# board.net
KiCad netlist of a schematic drawn in EAGLE
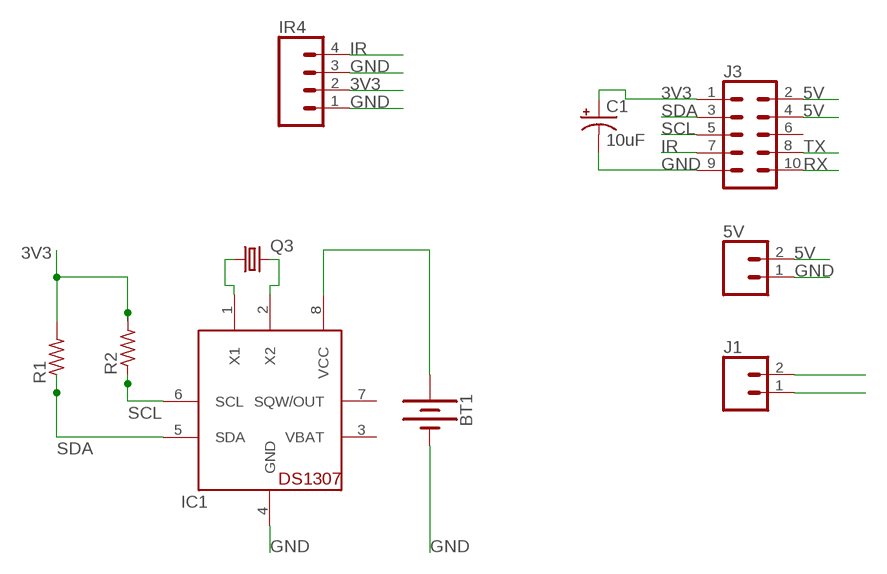
[diagram p0: schematic, sheet 1]

(export (version "E")
  (design (tool "Eeschema 10.0.6"))
  (components
    (comp (ref "5V")
      (value "CONN_02POLAR")
      (footprint "eagle-import:MOLEX-1X2")
      (libsource (lib "eagle-import") (part "CONN_02POLAR"))
    )
    (comp (ref "BT1")
      (value "BATTERY-20MM_PTH")
      (footprint "eagle-import:BATTCOM_20MM_PTH")
      (libsource (lib "eagle-import") (part "BATTERY-20MM_PTH"))
    )
    (comp (ref "C1")
      (value "10uF")
      (footprint "eagle-import:CPOL-RADIAL-2.5MM-5MM")
      (libsource (lib "eagle-import") (part "10UF-POLAR-RADIAL-2.5MM-25V-20%"))
    )
    (comp (ref "IC1")
      (value "DS1307")
      (footprint "eagle-import:DIL08")
      (libsource (lib "eagle-import") (part "DS1307"))
    )
    (comp (ref "IR4")
      (value "CONN_04POLAR")
      (footprint "eagle-import:MOLEX-1X4")
      (libsource (lib "eagle-import") (part "CONN_04POLAR"))
    )
    (comp (ref "J1")
      (value "CONN_02")
      (footprint "eagle-import:1X02")
      (libsource (lib "eagle-import") (part "CONN_02"))
    )
    (comp (ref "J3")
      (value "CONN_05X2SHD_LOCK")
      (footprint "eagle-import:2X5-SHROUDED_LOCK")
      (libsource (lib "eagle-import") (part "CONN_05X2SHD_LOCK"))
    )
    (comp (ref "Q3")
      (value "CRYSTALTC38H")
      (footprint "eagle-import:TC38H")
      (libsource (lib "eagle-import") (part "CRYSTALTC38H"))
    )
    (comp (ref "R1")
      (value "R-US_0204/7")
      (footprint "eagle-import:0204_7")
      (libsource (lib "eagle-import") (part "R-US_0204/7"))
    )
    (comp (ref "R2")
      (value "R-US_0204/7")
      (footprint "eagle-import:0204_7")
      (libsource (lib "eagle-import") (part "R-US_0204/7"))
    )
  )
  (nets
    (net (code "1") (name "/3V3") (class "Default")
      (node (ref "C1") (pin "1") (pinfunction "+_1") (pintype "passive"))
      (node (ref "IR4") (pin "2") (pinfunction "2_2") (pintype "passive"))
      (node (ref "J3") (pin "1") (pinfunction "1_1") (pintype "passive"))
      (node (ref "R1") (pin "2") (pinfunction "2_2") (pintype "passive"))
      (node (ref "R2") (pin "2") (pinfunction "2_2") (pintype "passive"))
    )
    (net (code "2") (name "/5V") (class "Default")
      (node (ref "5V") (pin "2") (pinfunction "2_2") (pintype "passive"))
      (node (ref "J3") (pin "2") (pinfunction "2_2") (pintype "passive"))
      (node (ref "J3") (pin "4") (pinfunction "4_4") (pintype "passive"))
    )
    (net (code "3") (name "/GND") (class "Default")
      (node (ref "5V") (pin "1") (pinfunction "1_1") (pintype "passive"))
      (node (ref "BT1") (pin "2") (pinfunction "-_2") (pintype "power_in"))
      (node (ref "C1") (pin "2") (pinfunction "-_2") (pintype "passive"))
      (node (ref "IC1") (pin "4") (pinfunction "GND_4") (pintype "power_in"))
      (node (ref "IR4") (pin "1") (pinfunction "1_1") (pintype "passive"))
      (node (ref "IR4") (pin "3") (pinfunction "3_3") (pintype "passive"))
      (node (ref "J3") (pin "9") (pinfunction "9_9") (pintype "passive"))
    )
    (net (code "4") (name "/IR") (class "Default")
      (node (ref "IR4") (pin "4") (pinfunction "4_4") (pintype "passive"))
      (node (ref "J3") (pin "7") (pinfunction "7_7") (pintype "passive"))
    )
    (net (code "5") (name "/RX") (class "Default")
      (node (ref "J1") (pin "1") (pinfunction "1_1") (pintype "passive"))
      (node (ref "J3") (pin "10") (pinfunction "10_10") (pintype "passive"))
    )
    (net (code "6") (name "/SCL") (class "Default")
      (node (ref "IC1") (pin "6") (pinfunction "SCL_6") (pintype "bidirectional"))
      (node (ref "J3") (pin "5") (pinfunction "5_5") (pintype "passive"))
      (node (ref "R2") (pin "1") (pinfunction "1_1") (pintype "passive"))
    )
    (net (code "7") (name "/SDA") (class "Default")
      (node (ref "IC1") (pin "5") (pinfunction "SDA_5") (pintype "bidirectional"))
      (node (ref "J3") (pin "3") (pinfunction "3_3") (pintype "passive"))
      (node (ref "R1") (pin "1") (pinfunction "1_1") (pintype "passive"))
    )
    (net (code "8") (name "/TX") (class "Default")
      (node (ref "J1") (pin "2") (pinfunction "2_2") (pintype "passive"))
      (node (ref "J3") (pin "8") (pinfunction "8_8") (pintype "passive"))
    )
    (net (code "9") (name "/VBAT") (class "Default")
      (node (ref "IC1") (pin "3") (pinfunction "VBAT_3") (pintype "power_in"))
    )
    (net (code "10") (name "Net-(BT1-+)") (class "Default")
      (node (ref "BT1") (pin "1") (pinfunction "+_1") (pintype "power_in"))
      (node (ref "IC1") (pin "8") (pinfunction "VCC_8") (pintype "power_in"))
    )
    (net (code "11") (name "Net-(IC1-X1)") (class "Default")
      (node (ref "IC1") (pin "1") (pinfunction "X1_1") (pintype "passive"))
      (node (ref "Q3") (pin "1") (pinfunction "1_1") (pintype "passive"))
    )
    (net (code "12") (name "Net-(IC1-X2)") (class "Default")
      (node (ref "IC1") (pin "2") (pinfunction "X2_2") (pintype "passive"))
      (node (ref "Q3") (pin "2") (pinfunction "2_2") (pintype "passive"))
    )
    (net (code "13") (name "unconnected-(IC1-SQW{slash}OUT-Pad7)") (class "Default")
      (node (ref "IC1") (pin "7") (pinfunction "SQW/OUT_7") (pintype "bidirectional"))
    )
    (net (code "14") (name "unconnected-(J3-Pad6)") (class "Default")
      (node (ref "J3") (pin "6") (pinfunction "6_6") (pintype "passive"))
    )
  )
)
